# EventCounter.net
KiCad netlist of a schematic drawn in EAGLE
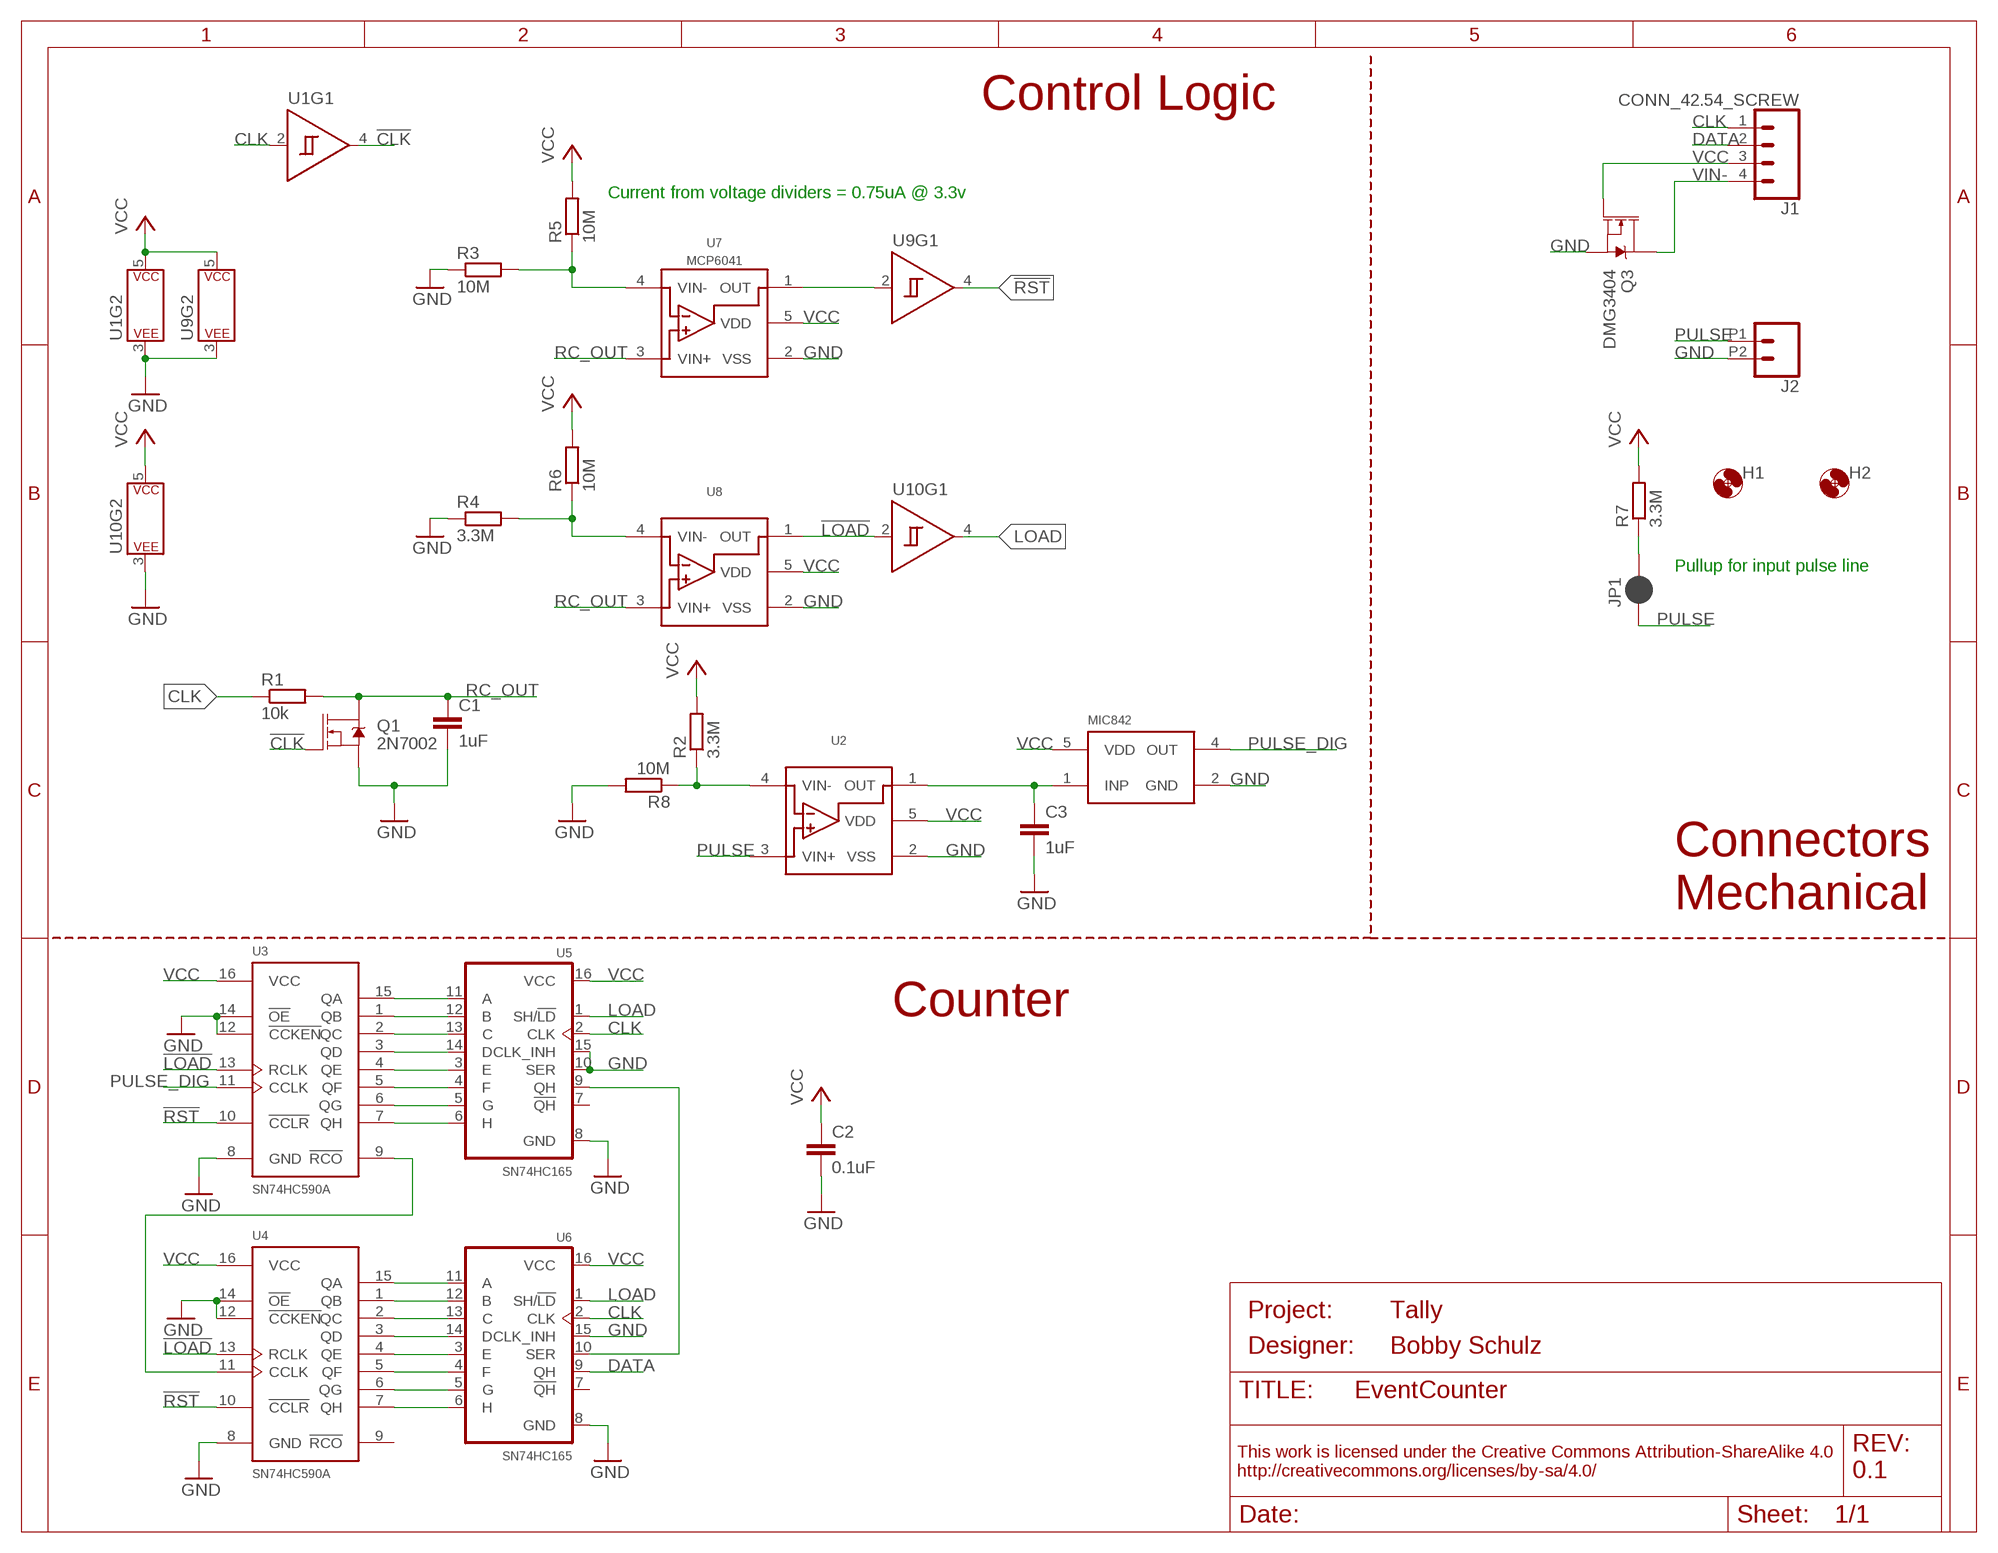
[diagram p0: schematic, sheet 1]

(export (version "E")
  (design (tool "Eeschema 10.0.6"))
  (components
    (comp (ref "C1")
      (value "1uF")
      (footprint "eagle-import:C0603")
      (fields (field (name "MF") "Samsung") (field (name "MPN") "1276-6524-1-ND"))
      (libsource (lib "eagle-import") (part "C-EUC06031UF"))
    )
    (comp (ref "C2")
      (value "0.1uF")
      (footprint "eagle-import:C0603")
      (fields (field (name "MF") "Murata") (field (name "MPN") "GCM188R71E104KA57D"))
      (libsource (lib "eagle-import") (part "C-EUC06030.1UF"))
    )
    (comp (ref "C3")
      (value "1uF")
      (footprint "eagle-import:C0603")
      (fields (field (name "MF") "Samsung") (field (name "MPN") "1276-6524-1-ND"))
      (libsource (lib "eagle-import") (part "C-EUC06031UF"))
    )
    (comp (ref "H1")
      (value "MOUNTING_HOLE2_NP")
      (footprint "eagle-import:2_56")
      (libsource (lib "eagle-import") (part "MOUNTING_HOLE2_NP"))
    )
    (comp (ref "H2")
      (value "MOUNTING_HOLE2_NP")
      (footprint "eagle-import:2_56")
      (libsource (lib "eagle-import") (part "MOUNTING_HOLE2_NP"))
    )
    (comp (ref "J1")
      (value "CONN_42.54_SCREW")
      (footprint "eagle-import:1X04_SCREW")
      (fields (field (name "MF") "On Shore") (field (name "MPN") "OSTVN04A150"))
      (libsource (lib "eagle-import") (part "CONN_42.54_SCREW"))
    )
    (comp (ref "J2")
      (value "CONN_02SCREW_2.54")
      (footprint "eagle-import:1X02_2.54_SCREWTERM")
      (fields (field (name "MF") "OnShore") (field (name "MPN") "OSTVN02A150"))
      (libsource (lib "eagle-import") (part "CONN_02SCREW_2.54"))
    )
    (comp (ref "JP1")
      (value "JUMPER-SMT_2_NC_PASTE_SILK")
      (footprint "eagle-import:SMT-JUMPER_2_NC_PASTE_SILK")
      (libsource (lib "eagle-import") (part "JUMPER-SMT_2_NC_PASTE_SILK"))
    )
    (comp (ref "Q1")
      (value "2N7002")
      (footprint "eagle-import:SOT323")
      (fields (field (name "MF") "Diodes Incorporated") (field (name "MPN") "2N7002W-7-F"))
      (libsource (lib "eagle-import") (part "MOSFET-NCH-2N7002PW"))
    )
    (comp (ref "Q3")
      (value "DMG3404")
      (footprint "eagle-import:SOT23-3")
      (fields (field (name "MF") "Diodes Incorporated") (field (name "MPN") "DMG3404L-7"))
      (libsource (lib "eagle-import") (part "MOSFET-NCH-DMG3404L"))
    )
    (comp (ref "R1")
      (value "10k")
      (footprint "eagle-import:R0603")
      (fields (field (name "MF") "Panasonic") (field (name "MPN") "ERJ-3EKF1002V"))
      (libsource (lib "eagle-import") (part "R-EU_R060310K"))
    )
    (comp (ref "R2")
      (value "3.3M")
      (footprint "eagle-import:R0603")
      (fields (field (name "MF") "Stackpole") (field (name "MPN") "RMCF0603FT3M30"))
      (libsource (lib "eagle-import") (part "R-EU_R06033.3M"))
    )
    (comp (ref "R3")
      (value "10M")
      (footprint "eagle-import:R0603")
      (fields (field (name "MF") "Stackpole") (field (name "MPN") "RMCF0603FT10M0"))
      (libsource (lib "eagle-import") (part "R-EU_R060310M"))
    )
    (comp (ref "R4")
      (value "3.3M")
      (footprint "eagle-import:R0603")
      (fields (field (name "MF") "Stackpole") (field (name "MPN") "RMCF0603FT3M30"))
      (libsource (lib "eagle-import") (part "R-EU_R06033.3M"))
    )
    (comp (ref "R5")
      (value "10M")
      (footprint "eagle-import:R0603")
      (fields (field (name "MF") "Stackpole") (field (name "MPN") "RMCF0603FT10M0"))
      (libsource (lib "eagle-import") (part "R-EU_R060310M"))
    )
    (comp (ref "R6")
      (value "10M")
      (footprint "eagle-import:R0603")
      (fields (field (name "MF") "Stackpole") (field (name "MPN") "RMCF0603FT10M0"))
      (libsource (lib "eagle-import") (part "R-EU_R060310M"))
    )
    (comp (ref "R7")
      (value "3.3M")
      (footprint "eagle-import:R0603")
      (fields (field (name "MF") "Stackpole") (field (name "MPN") "RMCF0603FT3M30"))
      (libsource (lib "eagle-import") (part "R-EU_R06033.3M"))
    )
    (comp (ref "R8")
      (value "10M")
      (footprint "eagle-import:R0603")
      (fields (field (name "MF") "Stackpole") (field (name "MPN") "RMCF0603FT10M0"))
      (libsource (lib "eagle-import") (part "R-EU_R060310M"))
    )
    (comp (ref "U$1")
      (value "MIC842H")
      (footprint "eagle-import:DCK_R-PDSO-G5")
      (fields (field (name "MF") "Microchip") (field (name "MPN") "MIC842HYC5-TR"))
      (libsource (lib "eagle-import") (part "MIC842H"))
    )
    (comp (ref "U1")
      (value "SN74LVC1G14DCK")
      (footprint "eagle-import:DCK_R-PDSO-G5")
      (fields (field (name "MF") "TI") (field (name "MPN") "SN74LVC1G14DCKR"))
      (libsource (lib "eagle-import") (part "SN741G14DCKLVC"))
    )
    (comp (ref "U2")
      (value "MCP6041")
      (footprint "eagle-import:SOT23-5")
      (fields (field (name "MF") "Microchip") (field (name "MPN") "MCP6041T-I/OT"))
      (libsource (lib "eagle-import") (part "MCP6041"))
    )
    (comp (ref "U3")
      (value "SN74HC590AD")
      (footprint "eagle-import:SO16")
      (fields (field (name "MF") "TI"))
      (libsource (lib "eagle-import") (part "SN74HC590AD"))
    )
    (comp (ref "U4")
      (value "SN74HC590AD")
      (footprint "eagle-import:SO16")
      (fields (field (name "MF") "TI"))
      (libsource (lib "eagle-import") (part "SN74HC590AD"))
    )
    (comp (ref "U5")
      (value "SN74HC165D")
      (footprint "eagle-import:SO16")
      (fields (field (name "MF") "TI") (field (name "MPN") "SN74HC165DR"))
      (libsource (lib "eagle-import") (part "SN74HC165D"))
    )
    (comp (ref "U6")
      (value "SN74HC165D")
      (footprint "eagle-import:SO16")
      (fields (field (name "MF") "TI") (field (name "MPN") "SN74HC165DR"))
      (libsource (lib "eagle-import") (part "SN74HC165D"))
    )
    (comp (ref "U7")
      (value "MCP6041")
      (footprint "eagle-import:SOT23-5")
      (fields (field (name "MF") "Microchip") (field (name "MPN") "MCP6041T-I/OT"))
      (libsource (lib "eagle-import") (part "MCP6041"))
    )
    (comp (ref "U8")
      (value "MCP6041")
      (footprint "eagle-import:SOT23-5")
      (fields
        (field (name "MF") "Microchip")
        (field (name "MPN") "MCP6041T-I/OT")
        (field (name "DISP") "MCP6041")
      )
      (libsource (lib "eagle-import") (part "MCP6041"))
    )
    (comp (ref "U9")
      (value "SN74LVC1G14DCK")
      (footprint "eagle-import:DCK_R-PDSO-G5")
      (fields (field (name "MF") "TI") (field (name "MPN") "SN74LVC1G14DCKR"))
      (libsource (lib "eagle-import") (part "SN741G14DCKLVC"))
    )
    (comp (ref "U10")
      (value "SN74LVC1G14DCK")
      (footprint "eagle-import:DCK_R-PDSO-G5")
      (fields (field (name "MF") "TI") (field (name "MPN") "SN74LVC1G14DCKR"))
      (libsource (lib "eagle-import") (part "SN741G14DCKLVC"))
    )
  )
  (nets
    (net (code "1") (name "/DATA") (class "Default")
      (node (ref "J1") (pin "2") (pinfunction "2_2") (pintype "passive"))
      (node (ref "U6") (pin "9") (pinfunction "QH_9") (pintype "tri_state"))
    )
    (net (code "2") (name "/PULSE") (class "Default")
      (node (ref "J2") (pin "P1") (pinfunction "1_P1") (pintype "passive"))
      (node (ref "JP1") (pin "1") (pinfunction "1_1") (pintype "passive"))
      (node (ref "U2") (pin "3") (pinfunction "VIN+_3") (pintype "input"))
    )
    (net (code "3") (name "/PULSE_DIG") (class "Default")
      (node (ref "U$1") (pin "4") (pinfunction "OUT_4") (pintype "output"))
      (node (ref "U3") (pin "11") (pinfunction "CCLK_11") (pintype "input"))
    )
    (net (code "4") (name "/RC_OUT") (class "Default")
      (node (ref "C1") (pin "1") (pinfunction "1_1") (pintype "passive"))
      (node (ref "Q1") (pin "3") (pinfunction "D_3") (pintype "bidirectional"))
      (node (ref "R1") (pin "2") (pinfunction "2_2") (pintype "passive"))
      (node (ref "U7") (pin "3") (pinfunction "VIN+_3") (pintype "input"))
      (node (ref "U8") (pin "3") (pinfunction "VIN+_3") (pintype "input"))
    )
    (net (code "5") (name "/VIN-") (class "Default")
      (node (ref "J1") (pin "4") (pinfunction "4_4") (pintype "passive"))
      (node (ref "Q3") (pin "3") (pinfunction "D_3") (pintype "bidirectional"))
    )
    (net (code "6") (name "/~{CLK}") (class "Default")
      (node (ref "Q1") (pin "1") (pinfunction "G_1") (pintype "bidirectional"))
      (node (ref "U1") (pin "4") (pinfunction "Y_4") (pintype "bidirectional"))
    )
    (net (code "7") (name "/~{LOAD}") (class "Default")
      (node (ref "U10") (pin "2") (pinfunction "A_2") (pintype "bidirectional"))
      (node (ref "U3") (pin "13") (pinfunction "RCLK_13") (pintype "input"))
      (node (ref "U4") (pin "13") (pinfunction "RCLK_13") (pintype "input"))
      (node (ref "U8") (pin "1") (pinfunction "OUT_1") (pintype "output"))
    )
    (net (code "8") (name "/~{RST}") (class "Default")
      (node (ref "U3") (pin "10") (pinfunction "~{CCLR}_10") (pintype "input"))
      (node (ref "U4") (pin "10") (pinfunction "~{CCLR}_10") (pintype "input"))
      (node (ref "U9") (pin "4") (pinfunction "Y_4") (pintype "bidirectional"))
    )
    (net (code "9") (name "CLK") (class "Default")
      (node (ref "J1") (pin "1") (pinfunction "1_1") (pintype "passive"))
      (node (ref "R1") (pin "1") (pinfunction "1_1") (pintype "passive"))
      (node (ref "U1") (pin "2") (pinfunction "A_2") (pintype "bidirectional"))
      (node (ref "U5") (pin "2") (pinfunction "CLK_2") (pintype "input"))
      (node (ref "U6") (pin "2") (pinfunction "CLK_2") (pintype "input"))
    )
    (net (code "10") (name "GND") (class "Default")
      (node (ref "C1") (pin "2") (pinfunction "2_2") (pintype "passive"))
      (node (ref "C2") (pin "2") (pinfunction "2_2") (pintype "passive"))
      (node (ref "C3") (pin "2") (pinfunction "2_2") (pintype "passive"))
      (node (ref "J2") (pin "P2") (pinfunction "2_P2") (pintype "passive"))
      (node (ref "Q1") (pin "2") (pinfunction "S_2") (pintype "bidirectional"))
      (node (ref "Q3") (pin "2") (pinfunction "S_2") (pintype "bidirectional"))
      (node (ref "R3") (pin "1") (pinfunction "1_1") (pintype "passive"))
      (node (ref "R4") (pin "1") (pinfunction "1_1") (pintype "passive"))
      (node (ref "R8") (pin "2") (pinfunction "2_2") (pintype "passive"))
      (node (ref "U$1") (pin "2") (pinfunction "GND_2") (pintype "power_in"))
      (node (ref "U1") (pin "3") (pinfunction "P$V-_3") (pintype "bidirectional"))
      (node (ref "U10") (pin "3") (pinfunction "P$V-_3") (pintype "bidirectional"))
      (node (ref "U2") (pin "2") (pinfunction "VSS_2") (pintype "power_in"))
      (node (ref "U3") (pin "12") (pinfunction "~{CCKEN}_12") (pintype "input"))
      (node (ref "U3") (pin "14") (pinfunction "~{OE}_14") (pintype "input"))
      (node (ref "U3") (pin "8") (pinfunction "GND_8") (pintype "power_in"))
      (node (ref "U4") (pin "12") (pinfunction "~{CCKEN}_12") (pintype "input"))
      (node (ref "U4") (pin "14") (pinfunction "~{OE}_14") (pintype "input"))
      (node (ref "U4") (pin "8") (pinfunction "GND_8") (pintype "power_in"))
      (node (ref "U5") (pin "10") (pinfunction "SER_10") (pintype "input"))
      (node (ref "U5") (pin "15") (pinfunction "CLK_INH_15") (pintype "input"))
      (node (ref "U5") (pin "8") (pinfunction "GND_8") (pintype "power_in"))
      (node (ref "U6") (pin "15") (pinfunction "CLK_INH_15") (pintype "input"))
      (node (ref "U6") (pin "8") (pinfunction "GND_8") (pintype "power_in"))
      (node (ref "U7") (pin "2") (pinfunction "VSS_2") (pintype "power_in"))
      (node (ref "U8") (pin "2") (pinfunction "VSS_2") (pintype "power_in"))
      (node (ref "U9") (pin "3") (pinfunction "P$V-_3") (pintype "bidirectional"))
    )
    (net (code "11") (name "LOAD") (class "Default")
      (node (ref "U10") (pin "4") (pinfunction "Y_4") (pintype "bidirectional"))
      (node (ref "U5") (pin "1") (pinfunction "SH/~{LD}_1") (pintype "input"))
      (node (ref "U6") (pin "1") (pinfunction "SH/~{LD}_1") (pintype "input"))
    )
    (net (code "12") (name "Net-(JP1-Pad2)") (class "Default")
      (node (ref "JP1") (pin "2") (pinfunction "2_2") (pintype "passive"))
      (node (ref "R7") (pin "1") (pinfunction "1_1") (pintype "passive"))
    )
    (net (code "13") (name "Net-(U$1-INP)") (class "Default")
      (node (ref "C3") (pin "1") (pinfunction "1_1") (pintype "passive"))
      (node (ref "U$1") (pin "1") (pinfunction "INP_1") (pintype "input"))
      (node (ref "U2") (pin "1") (pinfunction "OUT_1") (pintype "output"))
    )
    (net (code "14") (name "Net-(U2-VIN-)") (class "Default")
      (node (ref "R2") (pin "1") (pinfunction "1_1") (pintype "passive"))
      (node (ref "R8") (pin "1") (pinfunction "1_1") (pintype "passive"))
      (node (ref "U2") (pin "4") (pinfunction "VIN-_4") (pintype "input"))
    )
    (net (code "15") (name "Net-(U3-QA)") (class "Default")
      (node (ref "U3") (pin "15") (pinfunction "QA_15") (pintype "output"))
      (node (ref "U5") (pin "11") (pinfunction "A_11") (pintype "tri_state"))
    )
    (net (code "16") (name "Net-(U3-QB)") (class "Default")
      (node (ref "U3") (pin "1") (pinfunction "QB_1") (pintype "output"))
      (node (ref "U5") (pin "12") (pinfunction "B_12") (pintype "tri_state"))
    )
    (net (code "17") (name "Net-(U3-QC)") (class "Default")
      (node (ref "U3") (pin "2") (pinfunction "QC_2") (pintype "output"))
      (node (ref "U5") (pin "13") (pinfunction "C_13") (pintype "tri_state"))
    )
    (net (code "18") (name "Net-(U3-QD)") (class "Default")
      (node (ref "U3") (pin "3") (pinfunction "QD_3") (pintype "output"))
      (node (ref "U5") (pin "14") (pinfunction "D_14") (pintype "tri_state"))
    )
    (net (code "19") (name "Net-(U3-QE)") (class "Default")
      (node (ref "U3") (pin "4") (pinfunction "QE_4") (pintype "output"))
      (node (ref "U5") (pin "3") (pinfunction "E_3") (pintype "tri_state"))
    )
    (net (code "20") (name "Net-(U3-QF)") (class "Default")
      (node (ref "U3") (pin "5") (pinfunction "QF_5") (pintype "output"))
      (node (ref "U5") (pin "4") (pinfunction "F_4") (pintype "tri_state"))
    )
    (net (code "21") (name "Net-(U3-QG)") (class "Default")
      (node (ref "U3") (pin "6") (pinfunction "QG_6") (pintype "output"))
      (node (ref "U5") (pin "5") (pinfunction "G_5") (pintype "tri_state"))
    )
    (net (code "22") (name "Net-(U3-QH)") (class "Default")
      (node (ref "U3") (pin "7") (pinfunction "QH_7") (pintype "output"))
      (node (ref "U5") (pin "6") (pinfunction "H_6") (pintype "tri_state"))
    )
    (net (code "23") (name "Net-(U3-~{RCO})") (class "Default")
      (node (ref "U3") (pin "9") (pinfunction "~{RCO}_9") (pintype "output"))
      (node (ref "U4") (pin "11") (pinfunction "CCLK_11") (pintype "input"))
    )
    (net (code "24") (name "Net-(U4-QA)") (class "Default")
      (node (ref "U4") (pin "15") (pinfunction "QA_15") (pintype "output"))
      (node (ref "U6") (pin "11") (pinfunction "A_11") (pintype "tri_state"))
    )
    (net (code "25") (name "Net-(U4-QB)") (class "Default")
      (node (ref "U4") (pin "1") (pinfunction "QB_1") (pintype "output"))
      (node (ref "U6") (pin "12") (pinfunction "B_12") (pintype "tri_state"))
    )
    (net (code "26") (name "Net-(U4-QC)") (class "Default")
      (node (ref "U4") (pin "2") (pinfunction "QC_2") (pintype "output"))
      (node (ref "U6") (pin "13") (pinfunction "C_13") (pintype "tri_state"))
    )
    (net (code "27") (name "Net-(U4-QD)") (class "Default")
      (node (ref "U4") (pin "3") (pinfunction "QD_3") (pintype "output"))
      (node (ref "U6") (pin "14") (pinfunction "D_14") (pintype "tri_state"))
    )
    (net (code "28") (name "Net-(U4-QE)") (class "Default")
      (node (ref "U4") (pin "4") (pinfunction "QE_4") (pintype "output"))
      (node (ref "U6") (pin "3") (pinfunction "E_3") (pintype "tri_state"))
    )
    (net (code "29") (name "Net-(U4-QF)") (class "Default")
      (node (ref "U4") (pin "5") (pinfunction "QF_5") (pintype "output"))
      (node (ref "U6") (pin "4") (pinfunction "F_4") (pintype "tri_state"))
    )
    (net (code "30") (name "Net-(U4-QG)") (class "Default")
      (node (ref "U4") (pin "6") (pinfunction "QG_6") (pintype "output"))
      (node (ref "U6") (pin "5") (pinfunction "G_5") (pintype "tri_state"))
    )
    (net (code "31") (name "Net-(U4-QH)") (class "Default")
      (node (ref "U4") (pin "7") (pinfunction "QH_7") (pintype "output"))
      (node (ref "U6") (pin "6") (pinfunction "H_6") (pintype "tri_state"))
    )
    (net (code "32") (name "Net-(U5-QH)") (class "Default")
      (node (ref "U5") (pin "9") (pinfunction "QH_9") (pintype "tri_state"))
      (node (ref "U6") (pin "10") (pinfunction "SER_10") (pintype "input"))
    )
    (net (code "33") (name "Net-(U7-OUT)") (class "Default")
      (node (ref "U7") (pin "1") (pinfunction "OUT_1") (pintype "output"))
      (node (ref "U9") (pin "2") (pinfunction "A_2") (pintype "bidirectional"))
    )
    (net (code "34") (name "Net-(U7-VIN-)") (class "Default")
      (node (ref "R3") (pin "2") (pinfunction "2_2") (pintype "passive"))
      (node (ref "R5") (pin "1") (pinfunction "1_1") (pintype "passive"))
      (node (ref "U7") (pin "4") (pinfunction "VIN-_4") (pintype "input"))
    )
    (net (code "35") (name "Net-(U8-VIN-)") (class "Default")
      (node (ref "R4") (pin "2") (pinfunction "2_2") (pintype "passive"))
      (node (ref "R6") (pin "1") (pinfunction "1_1") (pintype "passive"))
      (node (ref "U8") (pin "4") (pinfunction "VIN-_4") (pintype "input"))
    )
    (net (code "36") (name "VCC") (class "Default")
      (node (ref "C2") (pin "1") (pinfunction "1_1") (pintype "passive"))
      (node (ref "J1") (pin "3") (pinfunction "3_3") (pintype "passive"))
      (node (ref "Q3") (pin "1") (pinfunction "G_1") (pintype "bidirectional"))
      (node (ref "R2") (pin "2") (pinfunction "2_2") (pintype "passive"))
      (node (ref "R5") (pin "2") (pinfunction "2_2") (pintype "passive"))
      (node (ref "R6") (pin "2") (pinfunction "2_2") (pintype "passive"))
      (node (ref "R7") (pin "2") (pinfunction "2_2") (pintype "passive"))
      (node (ref "U$1") (pin "5") (pinfunction "VDD_5") (pintype "power_in"))
      (node (ref "U1") (pin "5") (pinfunction "P$V+_5") (pintype "bidirectional"))
      (node (ref "U10") (pin "5") (pinfunction "P$V+_5") (pintype "bidirectional"))
      (node (ref "U2") (pin "5") (pinfunction "VDD_5") (pintype "power_in"))
      (node (ref "U3") (pin "16") (pinfunction "VCC_16") (pintype "power_in"))
      (node (ref "U4") (pin "16") (pinfunction "VCC_16") (pintype "power_in"))
      (node (ref "U5") (pin "16") (pinfunction "VCC_16") (pintype "power_in"))
      (node (ref "U6") (pin "16") (pinfunction "VCC_16") (pintype "power_in"))
      (node (ref "U7") (pin "5") (pinfunction "VDD_5") (pintype "power_in"))
      (node (ref "U8") (pin "5") (pinfunction "VDD_5") (pintype "power_in"))
      (node (ref "U9") (pin "5") (pinfunction "P$V+_5") (pintype "bidirectional"))
    )
    (net (code "37") (name "unconnected-(U4-~{RCO}-Pad9)") (class "Default")
      (node (ref "U4") (pin "9") (pinfunction "~{RCO}_9") (pintype "output"))
    )
    (net (code "38") (name "unconnected-(U5-~{QH}-Pad7)") (class "Default")
      (node (ref "U5") (pin "7") (pinfunction "~{QH}_7") (pintype "input"))
    )
    (net (code "39") (name "unconnected-(U6-~{QH}-Pad7)") (class "Default")
      (node (ref "U6") (pin "7") (pinfunction "~{QH}_7") (pintype "input"))
    )
  )
)
